# 1_2.net
KiCad netlist of a schematic drawn in Altium Designer
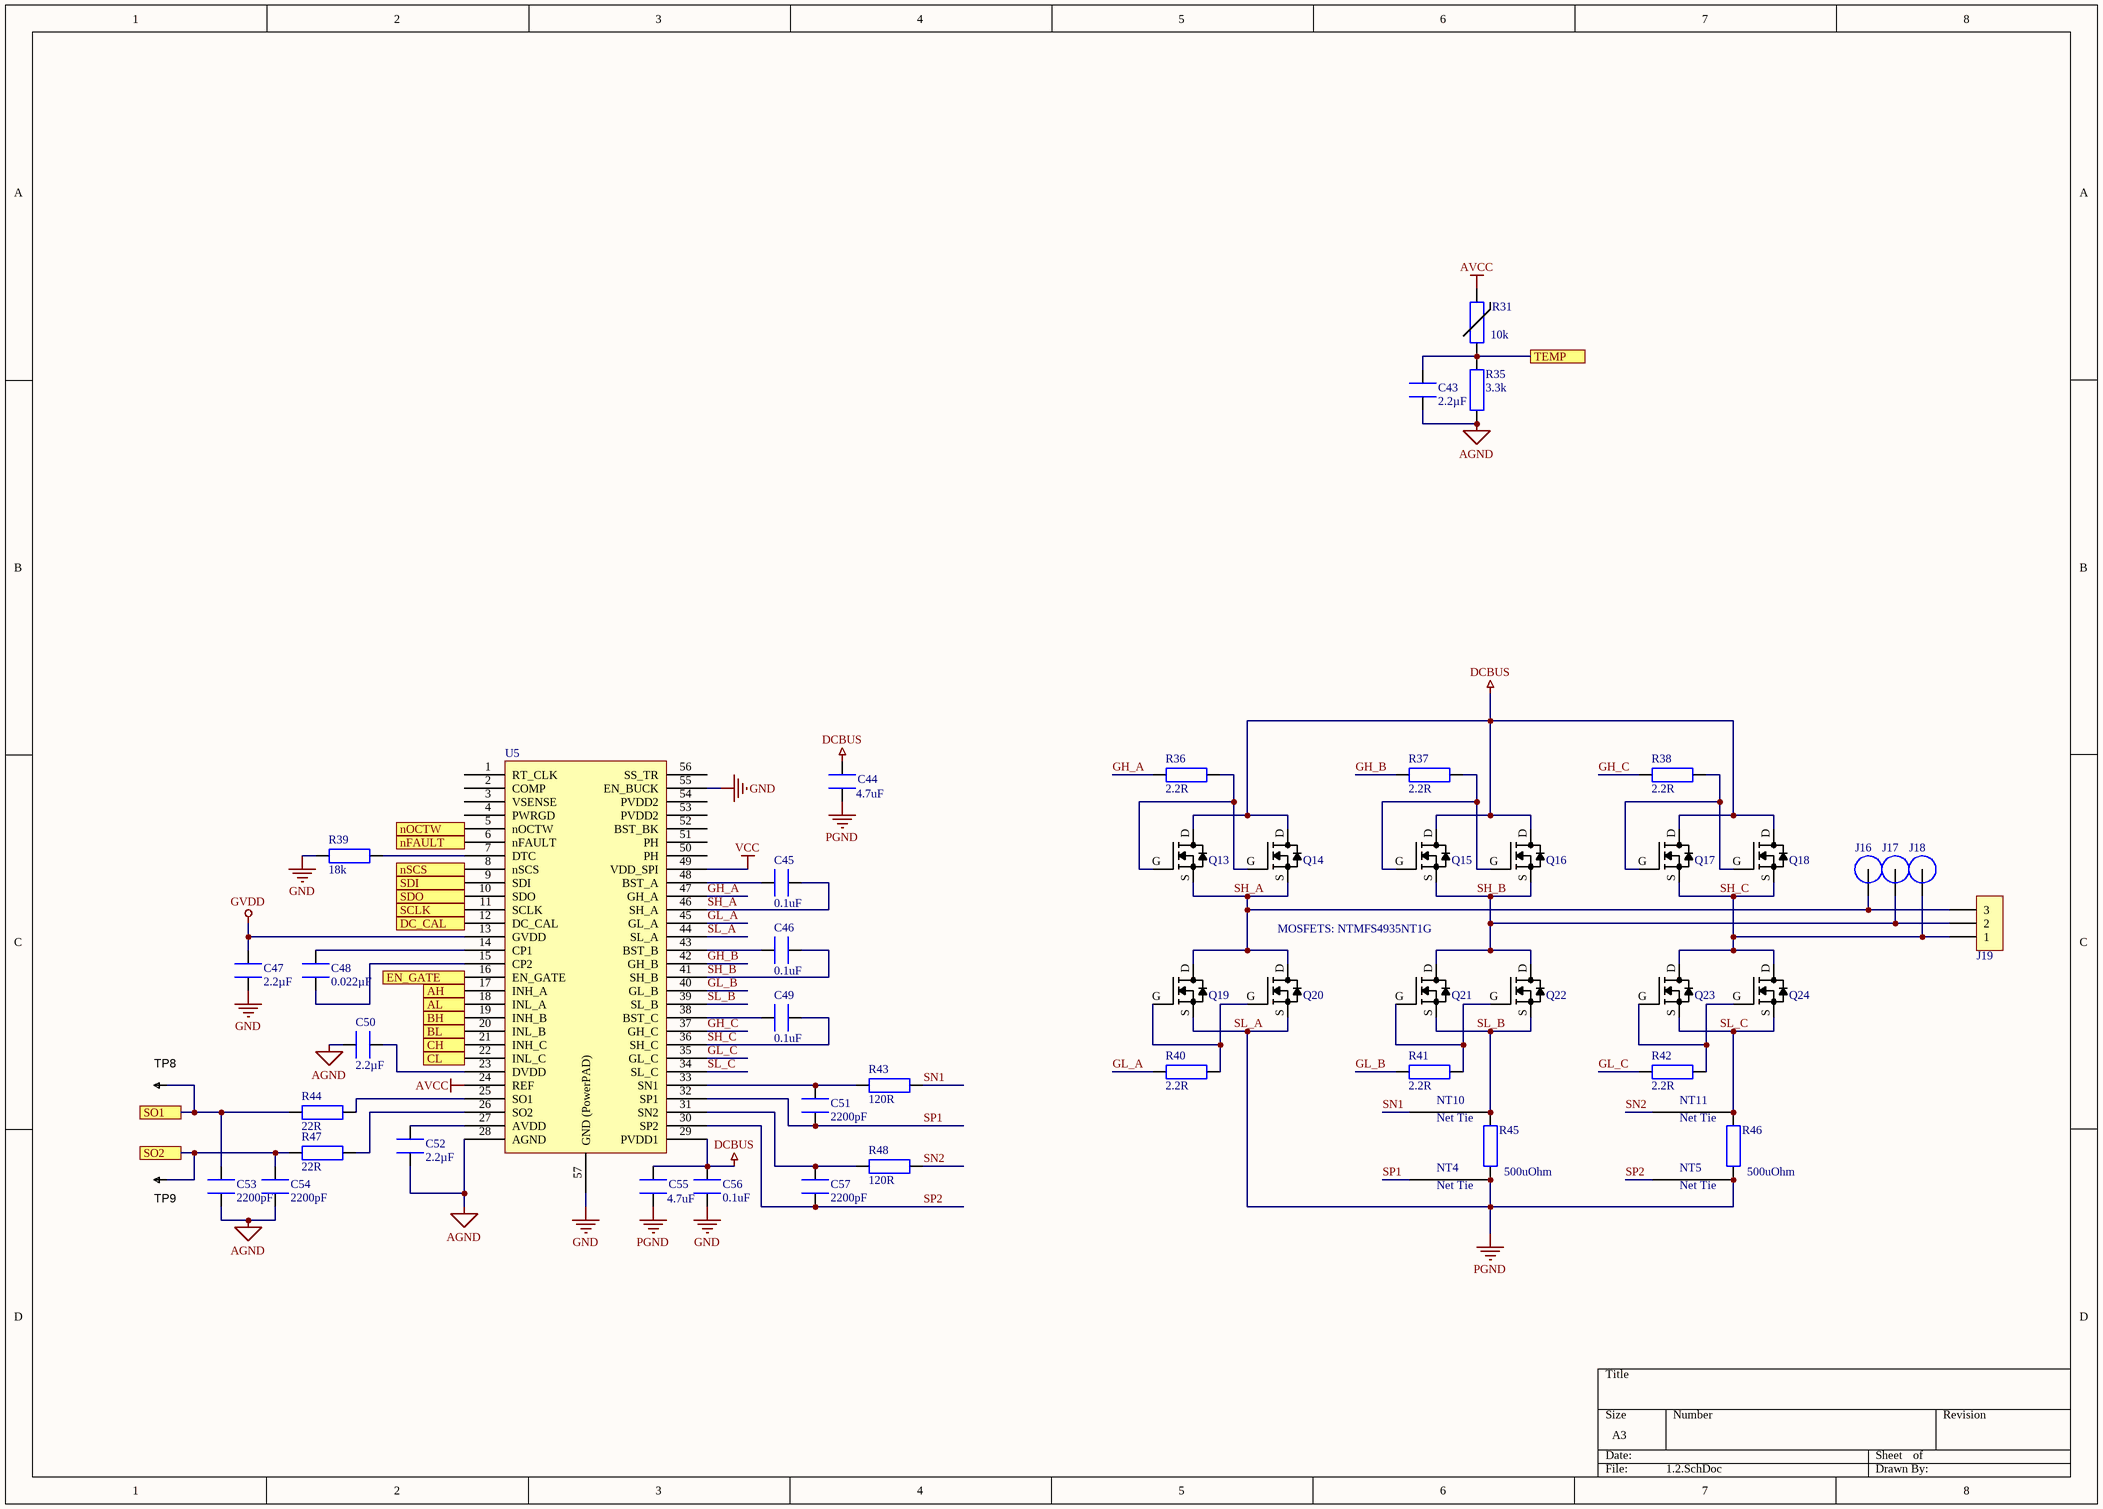
[diagram p0: 1.2.SchDoc]

(export (version "E")
  (design (tool "Eeschema 10.0.6"))
  (components
    (comp (ref "C43")
      (value "2.2µF")
      (footprint "CAPC1608X09L")
      (description "CAP CER 2.2UF 16V X5R 0603")
      (fields
        (field (name "MANUFACTURER") "Murata Electronics North America")
        (field (name "MANUFACTURER PART NUMBER") "GRM188R61C225KE15D")
      )
      (libsource (lib "CustomComponents") (part "GRM188R61C225KE15D"))
    )
    (comp (ref "C44")
      (value "4.7uF")
      (footprint "CAPC2012X09N")
      (description "CAP CER 4.7UF 35V X5R 0805")
      (fields
        (field (name "MANUFACTURER") "Murata Electronics North America")
        (field (name "TOLERANCE") "±10%")
      )
      (libsource (lib "CustomComponents") (part "GRM219R6YA475KA73D"))
    )
    (comp (ref "C45")
      (value "0.1uF")
      (footprint "CAPC1608X09L")
      (description "CAP CER 0.1UF 50V X7R 0603")
      (fields
        (field (name "MANUFACTURER") "Murata Electronics North America")
        (field (name "MANUFACTURER PART NUMBER") "GRM188R71H104KA93D")
      )
      (libsource (lib "CustomComponents") (part "GRM188R71H104KA93D"))
    )
    (comp (ref "C46")
      (value "0.1uF")
      (footprint "CAPC1608X09L")
      (description "CAP CER 0.1UF 50V X7R 0603")
      (fields
        (field (name "MANUFACTURER") "Murata Electronics North America")
        (field (name "MANUFACTURER PART NUMBER") "GRM188R71H104KA93D")
      )
      (libsource (lib "CustomComponents") (part "GRM188R71H104KA93D"))
    )
    (comp (ref "C47")
      (value "2.2µF")
      (footprint "CAPC1608X09L")
      (description "CAP CER 2.2UF 16V X5R 0603")
      (fields
        (field (name "MANUFACTURER") "Murata Electronics North America")
        (field (name "MANUFACTURER PART NUMBER") "GRM188R61C225KE15D")
      )
      (libsource (lib "CustomComponents") (part "GRM188R61C225KE15D"))
    )
    (comp (ref "C48")
      (value "0.022µF")
      (footprint "CAPC1608X09L")
      (description "CAP CER 0.022UF 50V X7R 0603")
      (fields
        (field (name "MANUFACTURER") "Murata Electronics North America")
        (field (name "MANUFACTURER PART NUMBER") "GRM188R71H223KA01D")
      )
      (libsource (lib "CustomComponents") (part "GRM188R71H223KA01D"))
    )
    (comp (ref "C49")
      (value "0.1uF")
      (footprint "CAPC1608X09L")
      (description "CAP CER 0.1UF 50V X7R 0603")
      (fields
        (field (name "MANUFACTURER") "Murata Electronics North America")
        (field (name "MANUFACTURER PART NUMBER") "GRM188R71H104KA93D")
      )
      (libsource (lib "CustomComponents") (part "GRM188R71H104KA93D"))
    )
    (comp (ref "C50")
      (value "2.2µF")
      (footprint "CAPC1608X09L")
      (description "CAP CER 2.2UF 16V X5R 0603")
      (fields
        (field (name "MANUFACTURER") "Murata Electronics North America")
        (field (name "MANUFACTURER PART NUMBER") "GRM188R61C225KE15D")
      )
      (libsource (lib "CustomComponents") (part "GRM188R61C225KE15D"))
    )
    (comp (ref "C51")
      (value "2200pF")
      (footprint "CAPC1608X09L")
      (description "CAP CER 2200PF 50V NP0 0603")
      (fields
        (field (name "MANUFACTURER") "Murata Electronics North America")
        (field (name "TOLERANCE") "±5%")
      )
      (libsource (lib "CustomComponents") (part "GRM1885C1H222JA01D"))
    )
    (comp (ref "C52")
      (value "2.2µF")
      (footprint "CAPC1608X09L")
      (description "CAP CER 2.2UF 16V X5R 0603")
      (fields
        (field (name "MANUFACTURER") "Murata Electronics North America")
        (field (name "MANUFACTURER PART NUMBER") "GRM188R61C225KE15D")
      )
      (libsource (lib "CustomComponents") (part "GRM188R61C225KE15D"))
    )
    (comp (ref "C53")
      (value "2200pF")
      (footprint "CAPC1608X09L")
      (description "CAP CER 2200PF 50V NP0 0603")
      (fields
        (field (name "MANUFACTURER") "Murata Electronics North America")
        (field (name "TOLERANCE") "±5%")
      )
      (libsource (lib "CustomComponents") (part "GRM1885C1H222JA01D"))
    )
    (comp (ref "C54")
      (value "2200pF")
      (footprint "CAPC1608X09L")
      (description "CAP CER 2200PF 50V NP0 0603")
      (fields
        (field (name "MANUFACTURER") "Murata Electronics North America")
        (field (name "TOLERANCE") "±5%")
      )
      (libsource (lib "CustomComponents") (part "GRM1885C1H222JA01D"))
    )
    (comp (ref "C55")
      (value "4.7uF")
      (footprint "CAPC2012X09N")
      (description "CAP CER 4.7UF 35V X5R 0805")
      (fields
        (field (name "MANUFACTURER") "Murata Electronics North America")
        (field (name "TOLERANCE") "±10%")
      )
      (libsource (lib "CustomComponents") (part "GRM219R6YA475KA73D"))
    )
    (comp (ref "C56")
      (value "0.1uF")
      (footprint "CAPC1608X09L")
      (description "CAP CER 0.1UF 50V X7R 0603")
      (fields
        (field (name "MANUFACTURER") "Murata Electronics North America")
        (field (name "MANUFACTURER PART NUMBER") "GRM188R71H104KA93D")
      )
      (libsource (lib "CustomComponents") (part "GRM188R71H104KA93D"))
    )
    (comp (ref "C57")
      (value "2200pF")
      (footprint "CAPC1608X09L")
      (description "CAP CER 2200PF 50V NP0 0603")
      (fields
        (field (name "MANUFACTURER") "Murata Electronics North America")
        (field (name "TOLERANCE") "±5%")
      )
      (libsource (lib "CustomComponents") (part "GRM1885C1H222JA01D"))
    )
    (comp (ref "J16")
      (value "~")
      (footprint "M3 Spade Hole")
      (description "M3 Spade Terminal")
      (libsource (lib "CustomComponents") (part "M3 Spade Terminal"))
    )
    (comp (ref "J17")
      (value "~")
      (footprint "M3 Spade Hole")
      (description "M3 Spade Terminal")
      (libsource (lib "CustomComponents") (part "M3 Spade Terminal"))
    )
    (comp (ref "J18")
      (value "~")
      (footprint "M3 Spade Hole")
      (description "M3 Spade Terminal")
      (libsource (lib "CustomComponents") (part "M3 Spade Terminal"))
    )
    (comp (ref "J19")
      (value "1704936")
      (footprint "1704936")
      (description "CONN TERM BLOCK 3POS 7.62MM")
      (fields (field (name "MANUFACTURER") "Phoenix Contact") (field (name "VOLTAGE") "300V"))
      (libsource (lib "CustomComponents") (part "1704936"))
    )
    (comp (ref "NT4")
      (value "0.25mm")
      (footprint "NetTie_0.25mm")
      (libsource (lib "CustomComponents") (part "NetTie_0.25mm"))
    )
    (comp (ref "NT5")
      (value "0.25mm")
      (footprint "NetTie_0.25mm")
      (libsource (lib "CustomComponents") (part "NetTie_0.25mm"))
    )
    (comp (ref "NT10")
      (value "0.25mm")
      (footprint "NetTie_0.25mm")
      (libsource (lib "CustomComponents") (part "NetTie_0.25mm"))
    )
    (comp (ref "NT11")
      (value "0.25mm")
      (footprint "NetTie_0.25mm")
      (libsource (lib "CustomComponents") (part "NetTie_0.25mm"))
    )
    (comp (ref "Q13")
      (value "~")
      (footprint "SO8FL")
      (description "MOSFET N-CH 30V 13A SO8FL")
      (fields
        (field (name "MANUFACTURER") "ON Semiconductor")
        (field (name "MANUFACTURER PART NUMBER") "NTMFS4935NT1G")
      )
      (libsource (lib "CustomComponents") (part "NTMFS4935NT1G"))
    )
    (comp (ref "Q14")
      (value "FILL_FOOTPRINT")
      (footprint "SO8FL_FILL")
      (description "MOSFET N-CH 30V 13A SO8FL")
      (fields
        (field (name "MANUFACTURER") "ON Semiconductor")
        (field (name "MANUFACTURER PART NUMBER") "NTMFS4935NT1G")
      )
      (libsource (lib "CustomComponents") (part "NTMFS4935NT1G"))
    )
    (comp (ref "Q15")
      (value "~")
      (footprint "SO8FL")
      (description "MOSFET N-CH 30V 13A SO8FL")
      (fields
        (field (name "MANUFACTURER") "ON Semiconductor")
        (field (name "MANUFACTURER PART NUMBER") "NTMFS4935NT1G")
      )
      (libsource (lib "CustomComponents") (part "NTMFS4935NT1G"))
    )
    (comp (ref "Q16")
      (value "FILL_FOOTPRINT")
      (footprint "SO8FL_FILL")
      (description "MOSFET N-CH 30V 13A SO8FL")
      (fields
        (field (name "MANUFACTURER") "ON Semiconductor")
        (field (name "MANUFACTURER PART NUMBER") "NTMFS4935NT1G")
      )
      (libsource (lib "CustomComponents") (part "NTMFS4935NT1G"))
    )
    (comp (ref "Q17")
      (value "~")
      (footprint "SO8FL")
      (description "MOSFET N-CH 30V 13A SO8FL")
      (fields
        (field (name "MANUFACTURER") "ON Semiconductor")
        (field (name "MANUFACTURER PART NUMBER") "NTMFS4935NT1G")
      )
      (libsource (lib "CustomComponents") (part "NTMFS4935NT1G"))
    )
    (comp (ref "Q18")
      (value "FILL_FOOTPRINT")
      (footprint "SO8FL_FILL")
      (description "MOSFET N-CH 30V 13A SO8FL")
      (fields
        (field (name "MANUFACTURER") "ON Semiconductor")
        (field (name "MANUFACTURER PART NUMBER") "NTMFS4935NT1G")
      )
      (libsource (lib "CustomComponents") (part "NTMFS4935NT1G"))
    )
    (comp (ref "Q19")
      (value "~")
      (footprint "SO8FL")
      (description "MOSFET N-CH 30V 13A SO8FL")
      (fields
        (field (name "MANUFACTURER") "ON Semiconductor")
        (field (name "MANUFACTURER PART NUMBER") "NTMFS4935NT1G")
      )
      (libsource (lib "CustomComponents") (part "NTMFS4935NT1G"))
    )
    (comp (ref "Q20")
      (value "~")
      (footprint "SO8FL")
      (description "MOSFET N-CH 30V 13A SO8FL")
      (fields
        (field (name "MANUFACTURER") "ON Semiconductor")
        (field (name "MANUFACTURER PART NUMBER") "NTMFS4935NT1G")
      )
      (libsource (lib "CustomComponents") (part "NTMFS4935NT1G"))
    )
    (comp (ref "Q21")
      (value "~")
      (footprint "SO8FL")
      (description "MOSFET N-CH 30V 13A SO8FL")
      (fields
        (field (name "MANUFACTURER") "ON Semiconductor")
        (field (name "MANUFACTURER PART NUMBER") "NTMFS4935NT1G")
      )
      (libsource (lib "CustomComponents") (part "NTMFS4935NT1G"))
    )
    (comp (ref "Q22")
      (value "~")
      (footprint "SO8FL")
      (description "MOSFET N-CH 30V 13A SO8FL")
      (fields
        (field (name "MANUFACTURER") "ON Semiconductor")
        (field (name "MANUFACTURER PART NUMBER") "NTMFS4935NT1G")
      )
      (libsource (lib "CustomComponents") (part "NTMFS4935NT1G"))
    )
    (comp (ref "Q23")
      (value "~")
      (footprint "SO8FL")
      (description "MOSFET N-CH 30V 13A SO8FL")
      (fields
        (field (name "MANUFACTURER") "ON Semiconductor")
        (field (name "MANUFACTURER PART NUMBER") "NTMFS4935NT1G")
      )
      (libsource (lib "CustomComponents") (part "NTMFS4935NT1G"))
    )
    (comp (ref "Q24")
      (value "~")
      (footprint "SO8FL")
      (description "MOSFET N-CH 30V 13A SO8FL")
      (fields
        (field (name "MANUFACTURER") "ON Semiconductor")
        (field (name "MANUFACTURER PART NUMBER") "NTMFS4935NT1G")
      )
      (libsource (lib "CustomComponents") (part "NTMFS4935NT1G"))
    )
    (comp (ref "R31")
      (value "10k")
      (footprint "RESC1005X40N")
      (description "THERMISTOR 10K OHM NTC 0402 SMD")
      (libsource (lib "CustomComponents") (part "NCP15XH103F03RC"))
    )
    (comp (ref "R35")
      (value "3.3k")
      (footprint "RESC1608X55N")
      (description "RES SMD 3.3K OHM 1% 1/10W 0603")
      (fields
        (field (name "MANUFACTURER") "Yageo")
        (field (name "MANUFACTURER PART NUMBER") "RC0603FR-073K3L")
      )
      (libsource (lib "CustomComponents") (part "RC0603FR-073K3L"))
    )
    (comp (ref "R36")
      (value "2.2R")
      (footprint "RESC1608X55N")
      (description "RES SMD 2.2 OHM 1% 1/10W 0603")
      (fields
        (field (name "MANUFACTURER") "Yageo")
        (field (name "MANUFACTURER PART NUMBER") "RC0603FR-072R2L")
      )
      (libsource (lib "CustomComponents") (part "RC0603FR-072R2L"))
    )
    (comp (ref "R37")
      (value "2.2R")
      (footprint "RESC1608X55N")
      (description "RES SMD 2.2 OHM 1% 1/10W 0603")
      (fields
        (field (name "MANUFACTURER") "Yageo")
        (field (name "MANUFACTURER PART NUMBER") "RC0603FR-072R2L")
      )
      (libsource (lib "CustomComponents") (part "RC0603FR-072R2L"))
    )
    (comp (ref "R38")
      (value "2.2R")
      (footprint "RESC1608X55N")
      (description "RES SMD 2.2 OHM 1% 1/10W 0603")
      (fields
        (field (name "MANUFACTURER") "Yageo")
        (field (name "MANUFACTURER PART NUMBER") "RC0603FR-072R2L")
      )
      (libsource (lib "CustomComponents") (part "RC0603FR-072R2L"))
    )
    (comp (ref "R39")
      (value "18k")
      (footprint "RESC1608X55N")
      (description "RES SMD 18K OHM 1% 1/10W 0603")
      (fields
        (field (name "MANUFACTURER") "Yageo")
        (field (name "MANUFACTURER PART NUMBER") "RC0603FR-0718KL")
      )
      (libsource (lib "CustomComponents") (part "RC0603FR-0718KL"))
    )
    (comp (ref "R40")
      (value "2.2R")
      (footprint "RESC1608X55N")
      (description "RES SMD 2.2 OHM 1% 1/10W 0603")
      (fields
        (field (name "MANUFACTURER") "Yageo")
        (field (name "MANUFACTURER PART NUMBER") "RC0603FR-072R2L")
      )
      (libsource (lib "CustomComponents") (part "RC0603FR-072R2L"))
    )
    (comp (ref "R41")
      (value "2.2R")
      (footprint "RESC1608X55N")
      (description "RES SMD 2.2 OHM 1% 1/10W 0603")
      (fields
        (field (name "MANUFACTURER") "Yageo")
        (field (name "MANUFACTURER PART NUMBER") "RC0603FR-072R2L")
      )
      (libsource (lib "CustomComponents") (part "RC0603FR-072R2L"))
    )
    (comp (ref "R42")
      (value "2.2R")
      (footprint "RESC1608X55N")
      (description "RES SMD 2.2 OHM 1% 1/10W 0603")
      (fields
        (field (name "MANUFACTURER") "Yageo")
        (field (name "MANUFACTURER PART NUMBER") "RC0603FR-072R2L")
      )
      (libsource (lib "CustomComponents") (part "RC0603FR-072R2L"))
    )
    (comp (ref "R43")
      (value "120R")
      (footprint "RESC1608X55N")
      (description "RES SMD 120 OHM 1% 1/10W 0603")
      (fields
        (field (name "MANUFACTURER") "Yageo")
        (field (name "MANUFACTURER PART NUMBER") "RC0603FR-07120RL")
      )
      (libsource (lib "CustomComponents") (part "RC0603FR-07120RL"))
    )
    (comp (ref "R44")
      (value "22R")
      (footprint "RESC1608X55N")
      (description "RES SMD 22 OHM 1% 1/10W 0603")
      (fields
        (field (name "MANUFACTURER") "Yageo")
        (field (name "MANUFACTURER PART NUMBER") "RC0603FR-0722RL")
      )
      (libsource (lib "CustomComponents") (part "RC0603FR-0722RL"))
    )
    (comp (ref "R45")
      (value "500uOhm")
      (footprint "RESC6432X09N")
      (description "RES SMD 0.0005 OHM 1% 3W 2512")
      (fields (field (name "MANUFACTURER") "Riedon") (field (name "TOLERANCE") "±1%"))
      (libsource (lib "CustomComponents") (part "CSR2512C0R0005F"))
    )
    (comp (ref "R46")
      (value "500uOhm")
      (footprint "RESC6432X09N")
      (description "RES SMD 0.0005 OHM 1% 3W 2512")
      (fields (field (name "MANUFACTURER") "Riedon") (field (name "TOLERANCE") "±1%"))
      (libsource (lib "CustomComponents") (part "CSR2512C0R0005F"))
    )
    (comp (ref "R47")
      (value "22R")
      (footprint "RESC1608X55N")
      (description "RES SMD 22 OHM 1% 1/10W 0603")
      (fields
        (field (name "MANUFACTURER") "Yageo")
        (field (name "MANUFACTURER PART NUMBER") "RC0603FR-0722RL")
      )
      (libsource (lib "CustomComponents") (part "RC0603FR-0722RL"))
    )
    (comp (ref "R48")
      (value "120R")
      (footprint "RESC1608X55N")
      (description "RES SMD 120 OHM 1% 1/10W 0603")
      (fields
        (field (name "MANUFACTURER") "Yageo")
        (field (name "MANUFACTURER PART NUMBER") "RC0603FR-07120RL")
      )
      (libsource (lib "CustomComponents") (part "RC0603FR-07120RL"))
    )
    (comp (ref "TP8")
      (value "TESTPOINT")
      (footprint "TP-R30")
      (description "SMD test pin")
      (libsource (lib "PBL - Test Points") (part "TESTPOINT"))
    )
    (comp (ref "TP9")
      (value "TESTPOINT")
      (footprint "TP-R30")
      (description "SMD test pin")
      (libsource (lib "PBL - Test Points") (part "TESTPOINT"))
    )
    (comp (ref "U5")
      (value "~")
      (footprint "TSSOP50P810X120_HS-57N")
      (description "MOTOR DRIVER, 3PH, 56HTSSOP")
      (libsource (lib "CustomComponents") (part "DRV8301"))
    )
  )
  (nets
    (net (code "1") (name "/AH") (class "Default")
      (node (ref "U5") (pin "17") (pinfunction "INH_A_17") (pintype "passive"))
    )
    (net (code "2") (name "/AL") (class "Default")
      (node (ref "U5") (pin "18") (pinfunction "INL_A_18") (pintype "passive"))
    )
    (net (code "3") (name "/BH") (class "Default")
      (node (ref "U5") (pin "19") (pinfunction "INH_B_19") (pintype "passive"))
    )
    (net (code "4") (name "/BL") (class "Default")
      (node (ref "U5") (pin "20") (pinfunction "INL_B_20") (pintype "passive"))
    )
    (net (code "5") (name "/CH") (class "Default")
      (node (ref "U5") (pin "21") (pinfunction "INH_C_21") (pintype "passive"))
    )
    (net (code "6") (name "/CL") (class "Default")
      (node (ref "U5") (pin "22") (pinfunction "INL_C_22") (pintype "passive"))
    )
    (net (code "7") (name "/DC_CAL") (class "Default")
      (node (ref "U5") (pin "12") (pinfunction "DC_CAL_12") (pintype "passive"))
    )
    (net (code "8") (name "/EN_GATE") (class "Default")
      (node (ref "U5") (pin "16") (pinfunction "EN_GATE_16") (pintype "passive"))
    )
    (net (code "9") (name "/GH_A") (class "Default")
      (node (ref "R36") (pin "1") (pinfunction "0_1") (pintype "passive"))
      (node (ref "U5") (pin "47") (pinfunction "GH_A_47") (pintype "passive"))
    )
    (net (code "10") (name "/GH_B") (class "Default")
      (node (ref "R37") (pin "1") (pinfunction "0_1") (pintype "passive"))
      (node (ref "U5") (pin "42") (pinfunction "GH_B_42") (pintype "passive"))
    )
    (net (code "11") (name "/GH_C") (class "Default")
      (node (ref "R38") (pin "1") (pinfunction "0_1") (pintype "passive"))
      (node (ref "U5") (pin "37") (pinfunction "GH_C_37") (pintype "passive"))
    )
    (net (code "12") (name "/GL_A") (class "Default")
      (node (ref "R40") (pin "1") (pinfunction "0_1") (pintype "passive"))
      (node (ref "U5") (pin "45") (pinfunction "GL_A_45") (pintype "passive"))
    )
    (net (code "13") (name "/GL_B") (class "Default")
      (node (ref "R41") (pin "1") (pinfunction "0_1") (pintype "passive"))
      (node (ref "U5") (pin "40") (pinfunction "GL_B_40") (pintype "passive"))
    )
    (net (code "14") (name "/GL_C") (class "Default")
      (node (ref "R42") (pin "1") (pinfunction "0_1") (pintype "passive"))
      (node (ref "U5") (pin "35") (pinfunction "GL_C_35") (pintype "passive"))
    )
    (net (code "15") (name "/SCLK") (class "Default")
      (node (ref "U5") (pin "11") (pinfunction "SCLK_11") (pintype "passive"))
    )
    (net (code "16") (name "/SDI") (class "Default")
      (node (ref "U5") (pin "9") (pinfunction "SDI_9") (pintype "passive"))
    )
    (net (code "17") (name "/SDO") (class "Default")
      (node (ref "U5") (pin "10") (pinfunction "SDO_10") (pintype "passive"))
    )
    (net (code "18") (name "/SH_A") (class "Default")
      (node (ref "C45") (pin "1") (pinfunction "1_1") (pintype "passive"))
      (node (ref "J16") (pin "1") (pinfunction "1_1") (pintype "passive"))
      (node (ref "J19") (pin "3") (pinfunction "3_3") (pintype "passive"))
      (node (ref "Q13") (pin "S") (pinfunction "S_S") (pintype "passive"))
      (node (ref "Q14") (pin "S") (pinfunction "S_S") (pintype "passive"))
      (node (ref "Q19") (pin "D") (pinfunction "D_D") (pintype "passive"))
      (node (ref "Q20") (pin "D") (pinfunction "D_D") (pintype "passive"))
      (node (ref "U5") (pin "46") (pinfunction "SH_A_46") (pintype "passive"))
    )
    (net (code "19") (name "/SH_B") (class "Default")
      (node (ref "C46") (pin "1") (pinfunction "1_1") (pintype "passive"))
      (node (ref "J17") (pin "1") (pinfunction "1_1") (pintype "passive"))
      (node (ref "J19") (pin "2") (pinfunction "2_2") (pintype "passive"))
      (node (ref "Q15") (pin "S") (pinfunction "S_S") (pintype "passive"))
      (node (ref "Q16") (pin "S") (pinfunction "S_S") (pintype "passive"))
      (node (ref "Q21") (pin "D") (pinfunction "D_D") (pintype "passive"))
      (node (ref "Q22") (pin "D") (pinfunction "D_D") (pintype "passive"))
      (node (ref "U5") (pin "41") (pinfunction "SH_B_41") (pintype "passive"))
    )
    (net (code "20") (name "/SH_C") (class "Default")
      (node (ref "C49") (pin "1") (pinfunction "1_1") (pintype "passive"))
      (node (ref "J18") (pin "1") (pinfunction "1_1") (pintype "passive"))
      (node (ref "J19") (pin "1") (pinfunction "1_1") (pintype "passive"))
      (node (ref "Q17") (pin "S") (pinfunction "S_S") (pintype "passive"))
      (node (ref "Q18") (pin "S") (pinfunction "S_S") (pintype "passive"))
      (node (ref "Q23") (pin "D") (pinfunction "D_D") (pintype "passive"))
      (node (ref "Q24") (pin "D") (pinfunction "D_D") (pintype "passive"))
      (node (ref "U5") (pin "36") (pinfunction "SH_C_36") (pintype "passive"))
    )
    (net (code "21") (name "/SL_B") (class "Default")
      (node (ref "NT10") (pin "2") (pintype "passive"))
      (node (ref "Q21") (pin "S") (pinfunction "S_S") (pintype "passive"))
      (node (ref "Q22") (pin "S") (pinfunction "S_S") (pintype "passive"))
      (node (ref "R45") (pin "2") (pinfunction "0_2") (pintype "passive"))
      (node (ref "U5") (pin "39") (pinfunction "SL_B_39") (pintype "passive"))
    )
    (net (code "22") (name "/SL_C") (class "Default")
      (node (ref "NT11") (pin "2") (pintype "passive"))
      (node (ref "Q23") (pin "S") (pinfunction "S_S") (pintype "passive"))
      (node (ref "Q24") (pin "S") (pinfunction "S_S") (pintype "passive"))
      (node (ref "R46") (pin "2") (pinfunction "0_2") (pintype "passive"))
      (node (ref "U5") (pin "34") (pinfunction "SL_C_34") (pintype "passive"))
    )
    (net (code "23") (name "/SN1") (class "Default")
      (node (ref "NT10") (pin "1") (pintype "passive"))
      (node (ref "R43") (pin "1") (pinfunction "0_1") (pintype "passive"))
    )
    (net (code "24") (name "/SN2") (class "Default")
      (node (ref "NT11") (pin "1") (pintype "passive"))
      (node (ref "R48") (pin "1") (pinfunction "0_1") (pintype "passive"))
    )
    (net (code "25") (name "/SO1") (class "Default")
      (node (ref "C53") (pin "1") (pinfunction "1_1") (pintype "passive"))
      (node (ref "R44") (pin "2") (pinfunction "0_2") (pintype "passive"))
      (node (ref "TP8") (pin "1") (pintype "passive"))
    )
    (net (code "26") (name "/SO2") (class "Default")
      (node (ref "C54") (pin "1") (pinfunction "1_1") (pintype "passive"))
      (node (ref "R47") (pin "2") (pinfunction "0_2") (pintype "passive"))
      (node (ref "TP9") (pin "1") (pintype "passive"))
    )
    (net (code "27") (name "/SP1") (class "Default")
      (node (ref "C51") (pin "2") (pinfunction "2_2") (pintype "passive"))
      (node (ref "NT4") (pin "1") (pintype "passive"))
      (node (ref "U5") (pin "32") (pinfunction "SP1_32") (pintype "passive"))
    )
    (net (code "28") (name "/SP2") (class "Default")
      (node (ref "C57") (pin "2") (pinfunction "2_2") (pintype "passive"))
      (node (ref "NT5") (pin "1") (pintype "passive"))
      (node (ref "U5") (pin "30") (pinfunction "SP2_30") (pintype "passive"))
    )
    (net (code "29") (name "/TEMP") (class "Default")
      (node (ref "C43") (pin "2") (pinfunction "2_2") (pintype "passive"))
      (node (ref "R31") (pin "1") (pinfunction "0_1") (pintype "passive"))
      (node (ref "R35") (pin "1") (pinfunction "0_1") (pintype "passive"))
    )
    (net (code "30") (name "/nFAULT") (class "Default")
      (node (ref "U5") (pin "6") (pinfunction "nFAULT_6") (pintype "passive"))
    )
    (net (code "31") (name "/nOCTW") (class "Default")
      (node (ref "U5") (pin "5") (pinfunction "nOCTW_5") (pintype "passive"))
    )
    (net (code "32") (name "/nSCS") (class "Default")
      (node (ref "U5") (pin "8") (pinfunction "nSCS_8") (pintype "passive"))
    )
    (net (code "33") (name "AGND") (class "Default")
      (node (ref "C43") (pin "1") (pinfunction "1_1") (pintype "passive"))
      (node (ref "C50") (pin "1") (pinfunction "1_1") (pintype "passive"))
      (node (ref "C52") (pin "1") (pinfunction "1_1") (pintype "passive"))
      (node (ref "C53") (pin "2") (pinfunction "2_2") (pintype "passive"))
      (node (ref "C54") (pin "2") (pinfunction "2_2") (pintype "passive"))
      (node (ref "R35") (pin "2") (pinfunction "0_2") (pintype "passive"))
      (node (ref "U5") (pin "28") (pinfunction "AGND_28") (pintype "passive"))
    )
    (net (code "34") (name "AVCC") (class "Default")
      (node (ref "R31") (pin "2") (pinfunction "0_2") (pintype "passive"))
      (node (ref "U5") (pin "24") (pinfunction "REF_24") (pintype "passive"))
    )
    (net (code "35") (name "DCBUS") (class "Default")
      (node (ref "C44") (pin "2") (pinfunction "2_2") (pintype "passive"))
      (node (ref "C55") (pin "2") (pinfunction "2_2") (pintype "passive"))
      (node (ref "C56") (pin "1") (pinfunction "1_1") (pintype "passive"))
      (node (ref "Q13") (pin "D") (pinfunction "D_D") (pintype "passive"))
      (node (ref "Q14") (pin "D") (pinfunction "D_D") (pintype "passive"))
      (node (ref "Q15") (pin "D") (pinfunction "D_D") (pintype "passive"))
      (node (ref "Q16") (pin "D") (pinfunction "D_D") (pintype "passive"))
      (node (ref "Q17") (pin "D") (pinfunction "D_D") (pintype "passive"))
      (node (ref "Q18") (pin "D") (pinfunction "D_D") (pintype "passive"))
      (node (ref "U5") (pin "29") (pinfunction "PVDD1_29") (pintype "passive"))
    )
    (net (code "36") (name "GND") (class "Default")
      (node (ref "C47") (pin "1") (pinfunction "1_1") (pintype "passive"))
      (node (ref "C56") (pin "2") (pinfunction "2_2") (pintype "passive"))
      (node (ref "R39") (pin "2") (pinfunction "0_2") (pintype "passive"))
      (node (ref "U5") (pin "55") (pinfunction "EN_BUCK_55") (pintype "passive"))
      (node (ref "U5") (pin "57") (pinfunction "GND_(PowerPAD)_57") (pintype "passive"))
    )
    (net (code "37") (name "GVDD") (class "Default")
      (node (ref "C47") (pin "2") (pinfunction "2_2") (pintype "passive"))
      (node (ref "U5") (pin "13") (pinfunction "GVDD_13") (pintype "passive"))
    )
    (net (code "38") (name "Net-(Q13-PadG)") (class "Default")
      (node (ref "Q13") (pin "G") (pinfunction "G_G") (pintype "passive"))
      (node (ref "Q14") (pin "G") (pinfunction "G_G") (pintype "passive"))
      (node (ref "R36") (pin "2") (pinfunction "0_2") (pintype "passive"))
    )
    (net (code "39") (name "Net-(Q15-PadG)") (class "Default")
      (node (ref "Q15") (pin "G") (pinfunction "G_G") (pintype "passive"))
      (node (ref "Q16") (pin "G") (pinfunction "G_G") (pintype "passive"))
      (node (ref "R37") (pin "2") (pinfunction "0_2") (pintype "passive"))
    )
    (net (code "40") (name "Net-(Q17-PadG)") (class "Default")
      (node (ref "Q17") (pin "G") (pinfunction "G_G") (pintype "passive"))
      (node (ref "Q18") (pin "G") (pinfunction "G_G") (pintype "passive"))
      (node (ref "R38") (pin "2") (pinfunction "0_2") (pintype "passive"))
    )
    (net (code "41") (name "Net-(Q19-PadG)") (class "Default")
      (node (ref "Q19") (pin "G") (pinfunction "G_G") (pintype "passive"))
      (node (ref "Q20") (pin "G") (pinfunction "G_G") (pintype "passive"))
      (node (ref "R40") (pin "2") (pinfunction "0_2") (pintype "passive"))
    )
    (net (code "42") (name "Net-(Q21-PadG)") (class "Default")
      (node (ref "Q21") (pin "G") (pinfunction "G_G") (pintype "passive"))
      (node (ref "Q22") (pin "G") (pinfunction "G_G") (pintype "passive"))
      (node (ref "R41") (pin "2") (pinfunction "0_2") (pintype "passive"))
    )
    (net (code "43") (name "Net-(Q23-PadG)") (class "Default")
      (node (ref "Q23") (pin "G") (pinfunction "G_G") (pintype "passive"))
      (node (ref "Q24") (pin "G") (pinfunction "G_G") (pintype "passive"))
      (node (ref "R42") (pin "2") (pinfunction "0_2") (pintype "passive"))
    )
    (net (code "44") (name "Net-(U5-AVDD)") (class "Default")
      (node (ref "C52") (pin "2") (pinfunction "2_2") (pintype "passive"))
      (node (ref "U5") (pin "27") (pinfunction "AVDD_27") (pintype "passive"))
    )
    (net (code "45") (name "Net-(U5-BST_A)") (class "Default")
      (node (ref "C45") (pin "2") (pinfunction "2_2") (pintype "passive"))
      (node (ref "U5") (pin "48") (pinfunction "BST_A_48") (pintype "passive"))
    )
    (net (code "46") (name "Net-(U5-BST_B)") (class "Default")
      (node (ref "C46") (pin "2") (pinfunction "2_2") (pintype "passive"))
      (node (ref "U5") (pin "43") (pinfunction "BST_B_43") (pintype "passive"))
    )
    (net (code "47") (name "Net-(U5-BST_C)") (class "Default")
      (node (ref "C49") (pin "2") (pinfunction "2_2") (pintype "passive"))
      (node (ref "U5") (pin "38") (pinfunction "BST_C_38") (pintype "passive"))
    )
    (net (code "48") (name "Net-(U5-CP1)") (class "Default")
      (node (ref "C48") (pin "1") (pinfunction "1_1") (pintype "passive"))
      (node (ref "U5") (pin "14") (pinfunction "CP1_14") (pintype "passive"))
    )
    (net (code "49") (name "Net-(U5-CP2)") (class "Default")
      (node (ref "C48") (pin "2") (pinfunction "2_2") (pintype "passive"))
      (node (ref "U5") (pin "15") (pinfunction "CP2_15") (pintype "passive"))
    )
    (net (code "50") (name "Net-(U5-DTC)") (class "Default")
      (node (ref "R39") (pin "1") (pinfunction "0_1") (pintype "passive"))
      (node (ref "U5") (pin "7") (pinfunction "DTC_7") (pintype "passive"))
    )
    (net (code "51") (name "Net-(U5-DVDD)") (class "Default")
      (node (ref "C50") (pin "2") (pinfunction "2_2") (pintype "passive"))
      (node (ref "U5") (pin "23") (pinfunction "DVDD_23") (pintype "passive"))
    )
    (net (code "52") (name "Net-(U5-SN1)") (class "Default")
      (node (ref "C51") (pin "1") (pinfunction "1_1") (pintype "passive"))
      (node (ref "R43") (pin "2") (pinfunction "0_2") (pintype "passive"))
      (node (ref "U5") (pin "33") (pinfunction "SN1_33") (pintype "passive"))
    )
    (net (code "53") (name "Net-(U5-SN2)") (class "Default")
      (node (ref "C57") (pin "1") (pinfunction "1_1") (pintype "passive"))
      (node (ref "R48") (pin "2") (pinfunction "0_2") (pintype "passive"))
      (node (ref "U5") (pin "31") (pinfunction "SN2_31") (pintype "passive"))
    )
    (net (code "54") (name "Net-(U5-SO1)") (class "Default")
      (node (ref "R44") (pin "1") (pinfunction "0_1") (pintype "passive"))
      (node (ref "U5") (pin "25") (pinfunction "SO1_25") (pintype "passive"))
    )
    (net (code "55") (name "Net-(U5-SO2)") (class "Default")
      (node (ref "R47") (pin "1") (pinfunction "0_1") (pintype "passive"))
      (node (ref "U5") (pin "26") (pinfunction "SO2_26") (pintype "passive"))
    )
    (net (code "56") (name "PGND") (class "Default")
      (node (ref "C44") (pin "1") (pinfunction "1_1") (pintype "passive"))
      (node (ref "C55") (pin "1") (pinfunction "1_1") (pintype "passive"))
      (node (ref "NT4") (pin "2") (pintype "passive"))
      (node (ref "NT5") (pin "2") (pintype "passive"))
      (node (ref "Q19") (pin "S") (pinfunction "S_S") (pintype "passive"))
      (node (ref "Q20") (pin "S") (pinfunction "S_S") (pintype "passive"))
      (node (ref "R45") (pin "1") (pinfunction "0_1") (pintype "passive"))
      (node (ref "R46") (pin "1") (pinfunction "0_1") (pintype "passive"))
      (node (ref "U5") (pin "44") (pinfunction "SL_A_44") (pintype "passive"))
    )
    (net (code "57") (name "VCC") (class "Default")
      (node (ref "U5") (pin "49") (pinfunction "VDD_SPI_49") (pintype "passive"))
    )
    (net (code "58") (name "unconnected-(U5-BST_BK-Pad52)") (class "Default")
      (node (ref "U5") (pin "52") (pinfunction "BST_BK_52") (pintype "passive"))
    )
    (net (code "59") (name "unconnected-(U5-COMP-Pad2)") (class "Default")
      (node (ref "U5") (pin "2") (pinfunction "COMP_2") (pintype "passive"))
    )
    (net (code "60") (name "unconnected-(U5-PH-Pad50)") (class "Default")
      (node (ref "U5") (pin "50") (pinfunction "PH_50") (pintype "passive"))
    )
    (net (code "61") (name "unconnected-(U5-PH-Pad51)") (class "Default")
      (node (ref "U5") (pin "51") (pinfunction "PH_51") (pintype "passive"))
    )
    (net (code "62") (name "unconnected-(U5-PVDD2-Pad53)") (class "Default")
      (node (ref "U5") (pin "53") (pinfunction "PVDD2_53") (pintype "passive"))
    )
    (net (code "63") (name "unconnected-(U5-PVDD2-Pad54)") (class "Default")
      (node (ref "U5") (pin "54") (pinfunction "PVDD2_54") (pintype "passive"))
    )
    (net (code "64") (name "unconnected-(U5-PWRGD-Pad4)") (class "Default")
      (node (ref "U5") (pin "4") (pinfunction "PWRGD_4") (pintype "passive"))
    )
    (net (code "65") (name "unconnected-(U5-RT_CLK-Pad1)") (class "Default")
      (node (ref "U5") (pin "1") (pinfunction "RT_CLK_1") (pintype "passive"))
    )
    (net (code "66") (name "unconnected-(U5-SS_TR-Pad56)") (class "Default")
      (node (ref "U5") (pin "56") (pinfunction "SS_TR_56") (pintype "passive"))
    )
    (net (code "67") (name "unconnected-(U5-VSENSE-Pad3)") (class "Default")
      (node (ref "U5") (pin "3") (pinfunction "VSENSE_3") (pintype "passive"))
    )
  )
)
